# sensor.net
KiCad netlist of a schematic drawn in Altium Designer
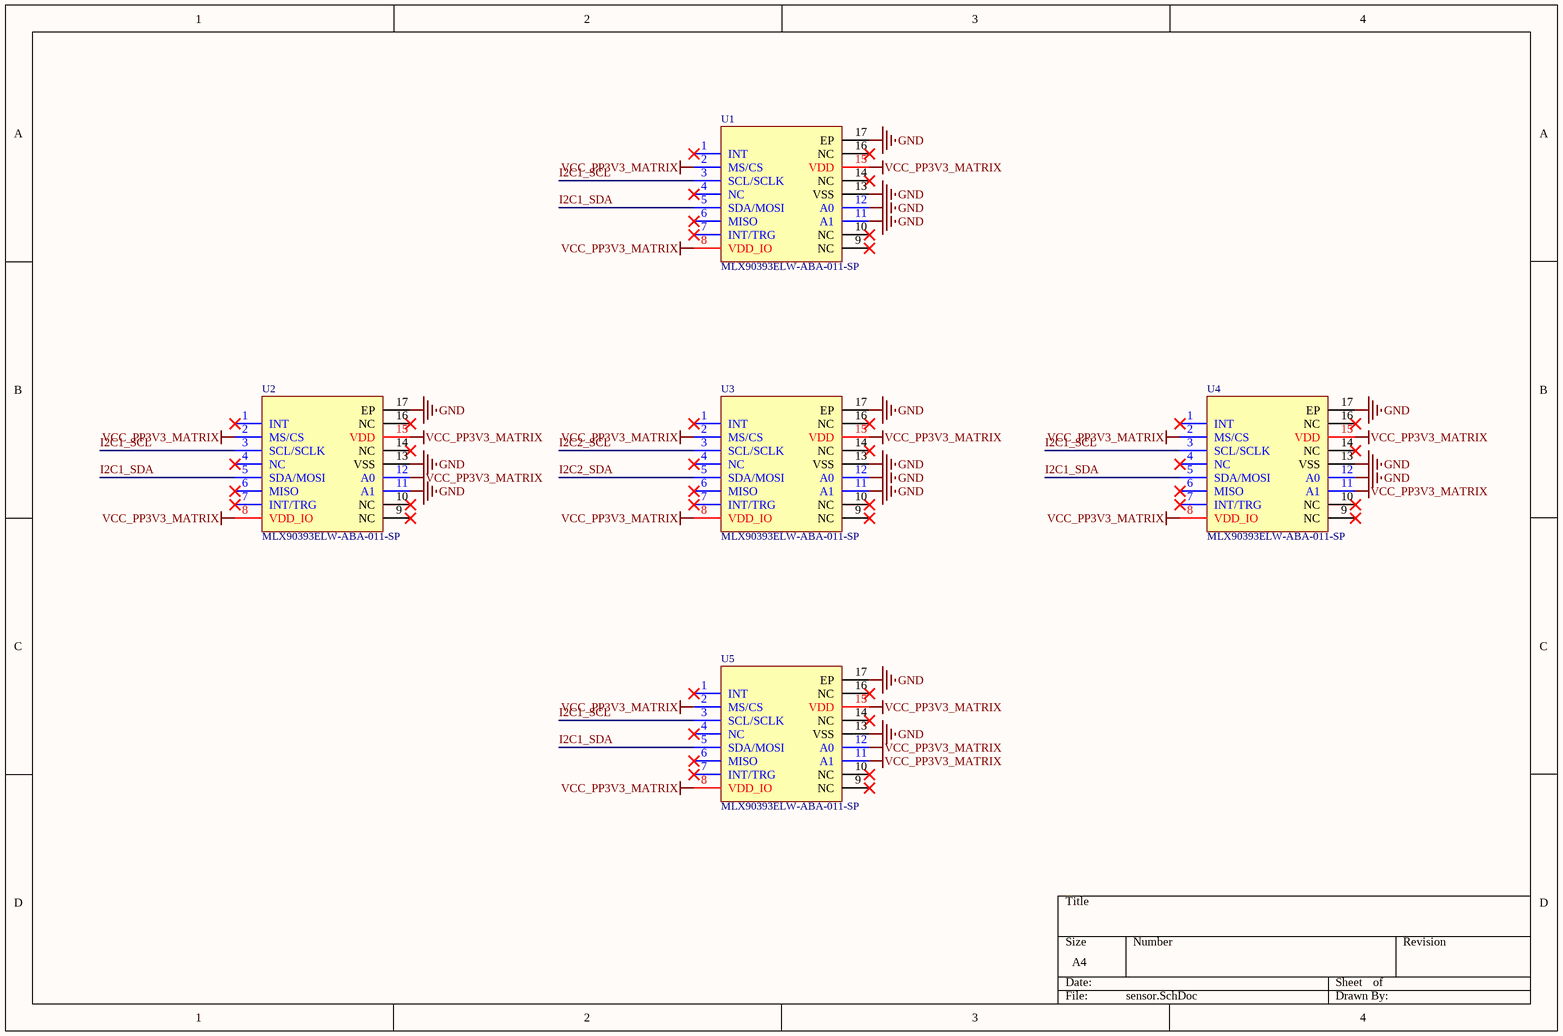
[diagram p0: sensor.SchDoc]

(export (version "E")
  (design (tool "Eeschema 10.0.6"))
  (components
    (comp (ref "U1")
      (value "MLX90393ELW-ABA-011-SP")
      (footprint "QFN-16_L3.0-W3.0-P0.50-TR-EP1.7")
      (description "3D磁传感器")
      (fields (field (name "BOM_SUPPLIER PART") "C1526586") (field (name "CONTRIBUTOR") "LCSC"))
      (libsource (lib "ullibs2") (part "MLX90393ELW-ABA-011-SP"))
    )
    (comp (ref "U2")
      (value "MLX90393ELW-ABA-011-SP")
      (footprint "QFN-16_L3.0-W3.0-P0.50-TR-EP1.7")
      (description "3D磁传感器")
      (fields (field (name "BOM_SUPPLIER PART") "C1526586") (field (name "CONTRIBUTOR") "LCSC"))
      (libsource (lib "ullibs2") (part "MLX90393ELW-ABA-011-SP"))
    )
    (comp (ref "U3")
      (value "MLX90393ELW-ABA-011-SP")
      (footprint "QFN-16_L3.0-W3.0-P0.50-TR-EP1.7")
      (description "3D磁传感器")
      (fields (field (name "BOM_SUPPLIER PART") "C1526586") (field (name "CONTRIBUTOR") "LCSC"))
      (libsource (lib "ullibs2") (part "MLX90393ELW-ABA-011-SP"))
    )
    (comp (ref "U4")
      (value "MLX90393ELW-ABA-011-SP")
      (footprint "QFN-16_L3.0-W3.0-P0.50-TR-EP1.7")
      (description "3D磁传感器")
      (fields (field (name "BOM_SUPPLIER PART") "C1526586") (field (name "CONTRIBUTOR") "LCSC"))
      (libsource (lib "ullibs2") (part "MLX90393ELW-ABA-011-SP"))
    )
    (comp (ref "U5")
      (value "MLX90393ELW-ABA-011-SP")
      (footprint "QFN-16_L3.0-W3.0-P0.50-TR-EP1.7")
      (description "3D磁传感器")
      (fields (field (name "BOM_SUPPLIER PART") "C1526586") (field (name "CONTRIBUTOR") "LCSC"))
      (libsource (lib "ullibs2") (part "MLX90393ELW-ABA-011-SP"))
    )
  )
  (nets
    (net (code "1") (name "/I2C1_SCL") (class "Default")
      (node (ref "U1") (pin "3") (pinfunction "SCL/SCLK_3") (pintype "passive"))
      (node (ref "U2") (pin "3") (pinfunction "SCL/SCLK_3") (pintype "passive"))
      (node (ref "U4") (pin "3") (pinfunction "SCL/SCLK_3") (pintype "passive"))
      (node (ref "U5") (pin "3") (pinfunction "SCL/SCLK_3") (pintype "passive"))
    )
    (net (code "2") (name "/I2C1_SDA") (class "Default")
      (node (ref "U1") (pin "5") (pinfunction "SDA/MOSI_5") (pintype "passive"))
      (node (ref "U2") (pin "5") (pinfunction "SDA/MOSI_5") (pintype "passive"))
      (node (ref "U4") (pin "5") (pinfunction "SDA/MOSI_5") (pintype "passive"))
      (node (ref "U5") (pin "5") (pinfunction "SDA/MOSI_5") (pintype "passive"))
    )
    (net (code "3") (name "/I2C2_SCL") (class "Default")
      (node (ref "U3") (pin "3") (pinfunction "SCL/SCLK_3") (pintype "passive"))
    )
    (net (code "4") (name "/I2C2_SDA") (class "Default")
      (node (ref "U3") (pin "5") (pinfunction "SDA/MOSI_5") (pintype "passive"))
    )
    (net (code "5") (name "GND") (class "Default")
      (node (ref "U1") (pin "11") (pinfunction "A1_11") (pintype "passive"))
      (node (ref "U1") (pin "12") (pinfunction "A0_12") (pintype "passive"))
      (node (ref "U1") (pin "13") (pinfunction "VSS_13") (pintype "passive"))
      (node (ref "U1") (pin "17") (pinfunction "EP_17") (pintype "passive"))
      (node (ref "U2") (pin "11") (pinfunction "A1_11") (pintype "passive"))
      (node (ref "U2") (pin "13") (pinfunction "VSS_13") (pintype "passive"))
      (node (ref "U2") (pin "17") (pinfunction "EP_17") (pintype "passive"))
      (node (ref "U3") (pin "11") (pinfunction "A1_11") (pintype "passive"))
      (node (ref "U3") (pin "12") (pinfunction "A0_12") (pintype "passive"))
      (node (ref "U3") (pin "13") (pinfunction "VSS_13") (pintype "passive"))
      (node (ref "U3") (pin "17") (pinfunction "EP_17") (pintype "passive"))
      (node (ref "U4") (pin "12") (pinfunction "A0_12") (pintype "passive"))
      (node (ref "U4") (pin "13") (pinfunction "VSS_13") (pintype "passive"))
      (node (ref "U4") (pin "17") (pinfunction "EP_17") (pintype "passive"))
      (node (ref "U5") (pin "13") (pinfunction "VSS_13") (pintype "passive"))
      (node (ref "U5") (pin "17") (pinfunction "EP_17") (pintype "passive"))
    )
    (net (code "6") (name "VCC_PP3V3_MATRIX") (class "Default")
      (node (ref "U1") (pin "15") (pinfunction "VDD_15") (pintype "passive"))
      (node (ref "U1") (pin "2") (pinfunction "MS/CS_2") (pintype "passive"))
      (node (ref "U1") (pin "8") (pinfunction "VDD_IO_8") (pintype "passive"))
      (node (ref "U2") (pin "12") (pinfunction "A0_12") (pintype "passive"))
      (node (ref "U2") (pin "15") (pinfunction "VDD_15") (pintype "passive"))
      (node (ref "U2") (pin "2") (pinfunction "MS/CS_2") (pintype "passive"))
      (node (ref "U2") (pin "8") (pinfunction "VDD_IO_8") (pintype "passive"))
      (node (ref "U3") (pin "15") (pinfunction "VDD_15") (pintype "passive"))
      (node (ref "U3") (pin "2") (pinfunction "MS/CS_2") (pintype "passive"))
      (node (ref "U3") (pin "8") (pinfunction "VDD_IO_8") (pintype "passive"))
      (node (ref "U4") (pin "11") (pinfunction "A1_11") (pintype "passive"))
      (node (ref "U4") (pin "15") (pinfunction "VDD_15") (pintype "passive"))
      (node (ref "U4") (pin "2") (pinfunction "MS/CS_2") (pintype "passive"))
      (node (ref "U4") (pin "8") (pinfunction "VDD_IO_8") (pintype "passive"))
      (node (ref "U5") (pin "11") (pinfunction "A1_11") (pintype "passive"))
      (node (ref "U5") (pin "12") (pinfunction "A0_12") (pintype "passive"))
      (node (ref "U5") (pin "15") (pinfunction "VDD_15") (pintype "passive"))
      (node (ref "U5") (pin "2") (pinfunction "MS/CS_2") (pintype "passive"))
      (node (ref "U5") (pin "8") (pinfunction "VDD_IO_8") (pintype "passive"))
    )
    (net (code "7") (name "unconnected-(U1-INT-Pad1)") (class "Default")
      (node (ref "U1") (pin "1") (pinfunction "INT_1") (pintype "passive+no_connect"))
    )
    (net (code "8") (name "unconnected-(U1-INT{slash}TRG-Pad7)") (class "Default")
      (node (ref "U1") (pin "7") (pinfunction "INT/TRG_7") (pintype "passive+no_connect"))
    )
    (net (code "9") (name "unconnected-(U1-MISO-Pad6)") (class "Default")
      (node (ref "U1") (pin "6") (pinfunction "MISO_6") (pintype "passive+no_connect"))
    )
    (net (code "10") (name "unconnected-(U1-NC-Pad4)") (class "Default")
      (node (ref "U1") (pin "4") (pinfunction "NC_4") (pintype "passive+no_connect"))
    )
    (net (code "11") (name "unconnected-(U1-NC-Pad9)") (class "Default")
      (node (ref "U1") (pin "9") (pinfunction "NC_9") (pintype "passive+no_connect"))
    )
    (net (code "12") (name "unconnected-(U1-NC-Pad10)") (class "Default")
      (node (ref "U1") (pin "10") (pinfunction "NC_10") (pintype "passive+no_connect"))
    )
    (net (code "13") (name "unconnected-(U1-NC-Pad14)") (class "Default")
      (node (ref "U1") (pin "14") (pinfunction "NC_14") (pintype "passive+no_connect"))
    )
    (net (code "14") (name "unconnected-(U1-NC-Pad16)") (class "Default")
      (node (ref "U1") (pin "16") (pinfunction "NC_16") (pintype "passive+no_connect"))
    )
    (net (code "15") (name "unconnected-(U2-INT-Pad1)") (class "Default")
      (node (ref "U2") (pin "1") (pinfunction "INT_1") (pintype "passive+no_connect"))
    )
    (net (code "16") (name "unconnected-(U2-INT{slash}TRG-Pad7)") (class "Default")
      (node (ref "U2") (pin "7") (pinfunction "INT/TRG_7") (pintype "passive+no_connect"))
    )
    (net (code "17") (name "unconnected-(U2-MISO-Pad6)") (class "Default")
      (node (ref "U2") (pin "6") (pinfunction "MISO_6") (pintype "passive+no_connect"))
    )
    (net (code "18") (name "unconnected-(U2-NC-Pad4)") (class "Default")
      (node (ref "U2") (pin "4") (pinfunction "NC_4") (pintype "passive+no_connect"))
    )
    (net (code "19") (name "unconnected-(U2-NC-Pad9)") (class "Default")
      (node (ref "U2") (pin "9") (pinfunction "NC_9") (pintype "passive+no_connect"))
    )
    (net (code "20") (name "unconnected-(U2-NC-Pad10)") (class "Default")
      (node (ref "U2") (pin "10") (pinfunction "NC_10") (pintype "passive+no_connect"))
    )
    (net (code "21") (name "unconnected-(U2-NC-Pad14)") (class "Default")
      (node (ref "U2") (pin "14") (pinfunction "NC_14") (pintype "passive+no_connect"))
    )
    (net (code "22") (name "unconnected-(U2-NC-Pad16)") (class "Default")
      (node (ref "U2") (pin "16") (pinfunction "NC_16") (pintype "passive+no_connect"))
    )
    (net (code "23") (name "unconnected-(U3-INT-Pad1)") (class "Default")
      (node (ref "U3") (pin "1") (pinfunction "INT_1") (pintype "passive+no_connect"))
    )
    (net (code "24") (name "unconnected-(U3-INT{slash}TRG-Pad7)") (class "Default")
      (node (ref "U3") (pin "7") (pinfunction "INT/TRG_7") (pintype "passive+no_connect"))
    )
    (net (code "25") (name "unconnected-(U3-MISO-Pad6)") (class "Default")
      (node (ref "U3") (pin "6") (pinfunction "MISO_6") (pintype "passive+no_connect"))
    )
    (net (code "26") (name "unconnected-(U3-NC-Pad4)") (class "Default")
      (node (ref "U3") (pin "4") (pinfunction "NC_4") (pintype "passive+no_connect"))
    )
    (net (code "27") (name "unconnected-(U3-NC-Pad9)") (class "Default")
      (node (ref "U3") (pin "9") (pinfunction "NC_9") (pintype "passive+no_connect"))
    )
    (net (code "28") (name "unconnected-(U3-NC-Pad10)") (class "Default")
      (node (ref "U3") (pin "10") (pinfunction "NC_10") (pintype "passive+no_connect"))
    )
    (net (code "29") (name "unconnected-(U3-NC-Pad14)") (class "Default")
      (node (ref "U3") (pin "14") (pinfunction "NC_14") (pintype "passive+no_connect"))
    )
    (net (code "30") (name "unconnected-(U3-NC-Pad16)") (class "Default")
      (node (ref "U3") (pin "16") (pinfunction "NC_16") (pintype "passive+no_connect"))
    )
    (net (code "31") (name "unconnected-(U4-INT-Pad1)") (class "Default")
      (node (ref "U4") (pin "1") (pinfunction "INT_1") (pintype "passive+no_connect"))
    )
    (net (code "32") (name "unconnected-(U4-INT{slash}TRG-Pad7)") (class "Default")
      (node (ref "U4") (pin "7") (pinfunction "INT/TRG_7") (pintype "passive+no_connect"))
    )
    (net (code "33") (name "unconnected-(U4-MISO-Pad6)") (class "Default")
      (node (ref "U4") (pin "6") (pinfunction "MISO_6") (pintype "passive+no_connect"))
    )
    (net (code "34") (name "unconnected-(U4-NC-Pad4)") (class "Default")
      (node (ref "U4") (pin "4") (pinfunction "NC_4") (pintype "passive+no_connect"))
    )
    (net (code "35") (name "unconnected-(U4-NC-Pad9)") (class "Default")
      (node (ref "U4") (pin "9") (pinfunction "NC_9") (pintype "passive+no_connect"))
    )
    (net (code "36") (name "unconnected-(U4-NC-Pad10)") (class "Default")
      (node (ref "U4") (pin "10") (pinfunction "NC_10") (pintype "passive+no_connect"))
    )
    (net (code "37") (name "unconnected-(U4-NC-Pad14)") (class "Default")
      (node (ref "U4") (pin "14") (pinfunction "NC_14") (pintype "passive+no_connect"))
    )
    (net (code "38") (name "unconnected-(U4-NC-Pad16)") (class "Default")
      (node (ref "U4") (pin "16") (pinfunction "NC_16") (pintype "passive+no_connect"))
    )
    (net (code "39") (name "unconnected-(U5-INT-Pad1)") (class "Default")
      (node (ref "U5") (pin "1") (pinfunction "INT_1") (pintype "passive+no_connect"))
    )
    (net (code "40") (name "unconnected-(U5-INT{slash}TRG-Pad7)") (class "Default")
      (node (ref "U5") (pin "7") (pinfunction "INT/TRG_7") (pintype "passive+no_connect"))
    )
    (net (code "41") (name "unconnected-(U5-MISO-Pad6)") (class "Default")
      (node (ref "U5") (pin "6") (pinfunction "MISO_6") (pintype "passive+no_connect"))
    )
    (net (code "42") (name "unconnected-(U5-NC-Pad4)") (class "Default")
      (node (ref "U5") (pin "4") (pinfunction "NC_4") (pintype "passive+no_connect"))
    )
    (net (code "43") (name "unconnected-(U5-NC-Pad9)") (class "Default")
      (node (ref "U5") (pin "9") (pinfunction "NC_9") (pintype "passive+no_connect"))
    )
    (net (code "44") (name "unconnected-(U5-NC-Pad10)") (class "Default")
      (node (ref "U5") (pin "10") (pinfunction "NC_10") (pintype "passive+no_connect"))
    )
    (net (code "45") (name "unconnected-(U5-NC-Pad14)") (class "Default")
      (node (ref "U5") (pin "14") (pinfunction "NC_14") (pintype "passive+no_connect"))
    )
    (net (code "46") (name "unconnected-(U5-NC-Pad16)") (class "Default")
      (node (ref "U5") (pin "16") (pinfunction "NC_16") (pintype "passive+no_connect"))
    )
  )
)
